# main_R1.net
KiCad netlist of a schematic drawn in EAGLE
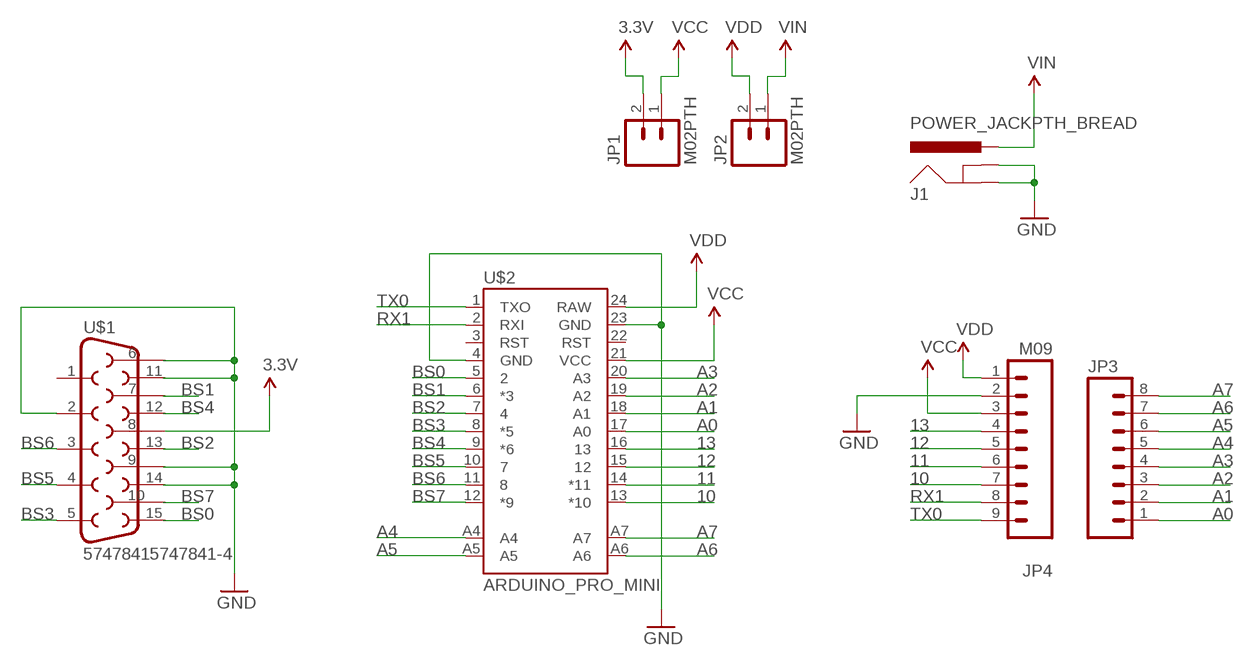
[diagram p0: schematic, sheet 1]

(export (version "E")
  (design (tool "Eeschema 10.0.6"))
  (components
    (comp (ref "J1")
      (value "POWER_JACKPTH_BREAD")
      (footprint "eagle-import:POWER_JACK_PTH_BREAD")
      (libsource (lib "eagle-import") (part "POWER_JACKPTH_BREAD"))
    )
    (comp (ref "JP1")
      (value "M02PTH")
      (footprint "eagle-import:1X02")
      (libsource (lib "eagle-import") (part "M02PTH"))
    )
    (comp (ref "JP2")
      (value "M02PTH")
      (footprint "eagle-import:1X02")
      (libsource (lib "eagle-import") (part "M02PTH"))
    )
    (comp (ref "JP3")
      (value "M081X08")
      (footprint "eagle-import:1X08")
      (libsource (lib "eagle-import") (part "M081X08"))
    )
    (comp (ref "JP4")
      (value "M09")
      (footprint "eagle-import:1X09")
      (libsource (lib "eagle-import") (part "M09"))
    )
    (comp (ref "U$1")
      (value "57478415747841-4")
      (footprint "eagle-import:5747841")
      (libsource (lib "eagle-import") (part "57478415747841-4"))
    )
    (comp (ref "U$2")
      (value "ARDUINO_PRO_MINI")
      (footprint "eagle-import:ARDUINO_PRO_MINI")
      (libsource (lib "eagle-import") (part "ARDUINO_PRO_MINI"))
    )
  )
  (nets
    (net (code "1") (name "/10") (class "Default")
      (node (ref "JP4") (pin "7") (pinfunction "7_7") (pintype "passive"))
      (node (ref "U$2") (pin "13") (pinfunction "*10_13") (pintype "bidirectional"))
    )
    (net (code "2") (name "/11") (class "Default")
      (node (ref "JP4") (pin "6") (pinfunction "6_6") (pintype "passive"))
      (node (ref "U$2") (pin "14") (pinfunction "*11_14") (pintype "bidirectional"))
    )
    (net (code "3") (name "/12") (class "Default")
      (node (ref "JP4") (pin "5") (pinfunction "5_5") (pintype "passive"))
      (node (ref "U$2") (pin "15") (pinfunction "12_15") (pintype "bidirectional"))
    )
    (net (code "4") (name "/13") (class "Default")
      (node (ref "JP4") (pin "4") (pinfunction "4_4") (pintype "passive"))
      (node (ref "U$2") (pin "16") (pinfunction "13_16") (pintype "bidirectional"))
    )
    (net (code "5") (name "/A0") (class "Default")
      (node (ref "JP3") (pin "1") (pinfunction "1_1") (pintype "passive"))
      (node (ref "U$2") (pin "17") (pinfunction "A0_17") (pintype "bidirectional"))
    )
    (net (code "6") (name "/A1") (class "Default")
      (node (ref "JP3") (pin "2") (pinfunction "2_2") (pintype "passive"))
      (node (ref "U$2") (pin "18") (pinfunction "A1_18") (pintype "bidirectional"))
    )
    (net (code "7") (name "/A2") (class "Default")
      (node (ref "JP3") (pin "3") (pinfunction "3_3") (pintype "passive"))
      (node (ref "U$2") (pin "19") (pinfunction "A2_19") (pintype "bidirectional"))
    )
    (net (code "8") (name "/A3") (class "Default")
      (node (ref "JP3") (pin "4") (pinfunction "4_4") (pintype "passive"))
      (node (ref "U$2") (pin "20") (pinfunction "A3_20") (pintype "bidirectional"))
    )
    (net (code "9") (name "/A4") (class "Default")
      (node (ref "JP3") (pin "5") (pinfunction "5_5") (pintype "passive"))
      (node (ref "U$2") (pin "A4") (pinfunction "A4_A4") (pintype "bidirectional"))
    )
    (net (code "10") (name "/A5") (class "Default")
      (node (ref "JP3") (pin "6") (pinfunction "6_6") (pintype "passive"))
      (node (ref "U$2") (pin "A5") (pinfunction "A5_A5") (pintype "bidirectional"))
    )
    (net (code "11") (name "/A6") (class "Default")
      (node (ref "JP3") (pin "7") (pinfunction "7_7") (pintype "passive"))
      (node (ref "U$2") (pin "A6") (pinfunction "A6_A6") (pintype "bidirectional"))
    )
    (net (code "12") (name "/A7") (class "Default")
      (node (ref "JP3") (pin "8") (pinfunction "8_8") (pintype "passive"))
      (node (ref "U$2") (pin "A7") (pinfunction "A7_A7") (pintype "bidirectional"))
    )
    (net (code "13") (name "/BS0") (class "Default")
      (node (ref "U$1") (pin "15") (pinfunction "15_15") (pintype "passive"))
      (node (ref "U$2") (pin "5") (pinfunction "2_5") (pintype "bidirectional"))
    )
    (net (code "14") (name "/BS1") (class "Default")
      (node (ref "U$1") (pin "7") (pinfunction "7_7") (pintype "passive"))
      (node (ref "U$2") (pin "6") (pinfunction "*3_6") (pintype "bidirectional"))
    )
    (net (code "15") (name "/BS2") (class "Default")
      (node (ref "U$1") (pin "13") (pinfunction "13_13") (pintype "passive"))
      (node (ref "U$2") (pin "7") (pinfunction "4_7") (pintype "bidirectional"))
    )
    (net (code "16") (name "/BS3") (class "Default")
      (node (ref "U$1") (pin "5") (pinfunction "5_5") (pintype "passive"))
      (node (ref "U$2") (pin "8") (pinfunction "*5_8") (pintype "bidirectional"))
    )
    (net (code "17") (name "/BS4") (class "Default")
      (node (ref "U$1") (pin "12") (pinfunction "12_12") (pintype "passive"))
      (node (ref "U$2") (pin "9") (pinfunction "*6_9") (pintype "bidirectional"))
    )
    (net (code "18") (name "/BS5") (class "Default")
      (node (ref "U$1") (pin "4") (pinfunction "4_4") (pintype "passive"))
      (node (ref "U$2") (pin "10") (pinfunction "7_10") (pintype "bidirectional"))
    )
    (net (code "19") (name "/BS6") (class "Default")
      (node (ref "U$1") (pin "3") (pinfunction "3_3") (pintype "passive"))
      (node (ref "U$2") (pin "11") (pinfunction "8_11") (pintype "bidirectional"))
    )
    (net (code "20") (name "/BS7") (class "Default")
      (node (ref "U$1") (pin "10") (pinfunction "10_10") (pintype "passive"))
      (node (ref "U$2") (pin "12") (pinfunction "*9_12") (pintype "bidirectional"))
    )
    (net (code "21") (name "/RX1") (class "Default")
      (node (ref "JP4") (pin "8") (pinfunction "8_8") (pintype "passive"))
      (node (ref "U$2") (pin "2") (pinfunction "RXI_2") (pintype "bidirectional"))
    )
    (net (code "22") (name "/TX0") (class "Default")
      (node (ref "JP4") (pin "9") (pinfunction "9_9") (pintype "passive"))
      (node (ref "U$2") (pin "1") (pinfunction "TXO_1") (pintype "bidirectional"))
    )
    (net (code "23") (name "3.3V") (class "Default")
      (node (ref "JP1") (pin "2") (pinfunction "2_2") (pintype "passive"))
      (node (ref "U$1") (pin "8") (pinfunction "8_8") (pintype "passive"))
    )
    (net (code "24") (name "GND") (class "Default")
      (node (ref "J1") (pin "GND") (pinfunction "GND_GND") (pintype "bidirectional"))
      (node (ref "J1") (pin "GNDBREAK") (pinfunction "GNDBREAK_GNDBREAK") (pintype "bidirectional"))
      (node (ref "JP4") (pin "2") (pinfunction "2_2") (pintype "passive"))
      (node (ref "U$1") (pin "11") (pinfunction "11_11") (pintype "passive"))
      (node (ref "U$1") (pin "14") (pinfunction "14_14") (pintype "passive"))
      (node (ref "U$1") (pin "2") (pinfunction "2_2") (pintype "passive"))
      (node (ref "U$1") (pin "6") (pinfunction "6_6") (pintype "passive"))
      (node (ref "U$1") (pin "9") (pinfunction "9_9") (pintype "passive"))
      (node (ref "U$2") (pin "23") (pinfunction "GND_23") (pintype "bidirectional"))
      (node (ref "U$2") (pin "4") (pinfunction "GND_4") (pintype "bidirectional"))
    )
    (net (code "25") (name "VCC") (class "Default")
      (node (ref "JP1") (pin "1") (pinfunction "1_1") (pintype "passive"))
      (node (ref "JP4") (pin "3") (pinfunction "3_3") (pintype "passive"))
      (node (ref "U$2") (pin "21") (pinfunction "VCC_21") (pintype "bidirectional"))
    )
    (net (code "26") (name "VDD") (class "Default")
      (node (ref "JP2") (pin "2") (pinfunction "2_2") (pintype "passive"))
      (node (ref "JP4") (pin "1") (pinfunction "1_1") (pintype "passive"))
      (node (ref "U$2") (pin "24") (pinfunction "RAW_24") (pintype "bidirectional"))
    )
    (net (code "27") (name "VIN") (class "Default")
      (node (ref "J1") (pin "PWR") (pinfunction "PWR_PWR") (pintype "bidirectional"))
      (node (ref "JP2") (pin "1") (pinfunction "1_1") (pintype "passive"))
    )
    (net (code "28") (name "unconnected-(U$1-Pad1)") (class "Default")
      (node (ref "U$1") (pin "1") (pinfunction "1_1") (pintype "passive"))
    )
    (net (code "29") (name "unconnected-(U$2-RST-Pad3)") (class "Default")
      (node (ref "U$2") (pin "3") (pinfunction "RST_3") (pintype "bidirectional"))
    )
    (net (code "30") (name "unconnected-(U$2-RST-Pad22)") (class "Default")
      (node (ref "U$2") (pin "22") (pinfunction "RST_22") (pintype "bidirectional"))
    )
  )
)
